# 780-00019_Rev1_Pg1.net
KiCad netlist of a schematic drawn in Altium Designer
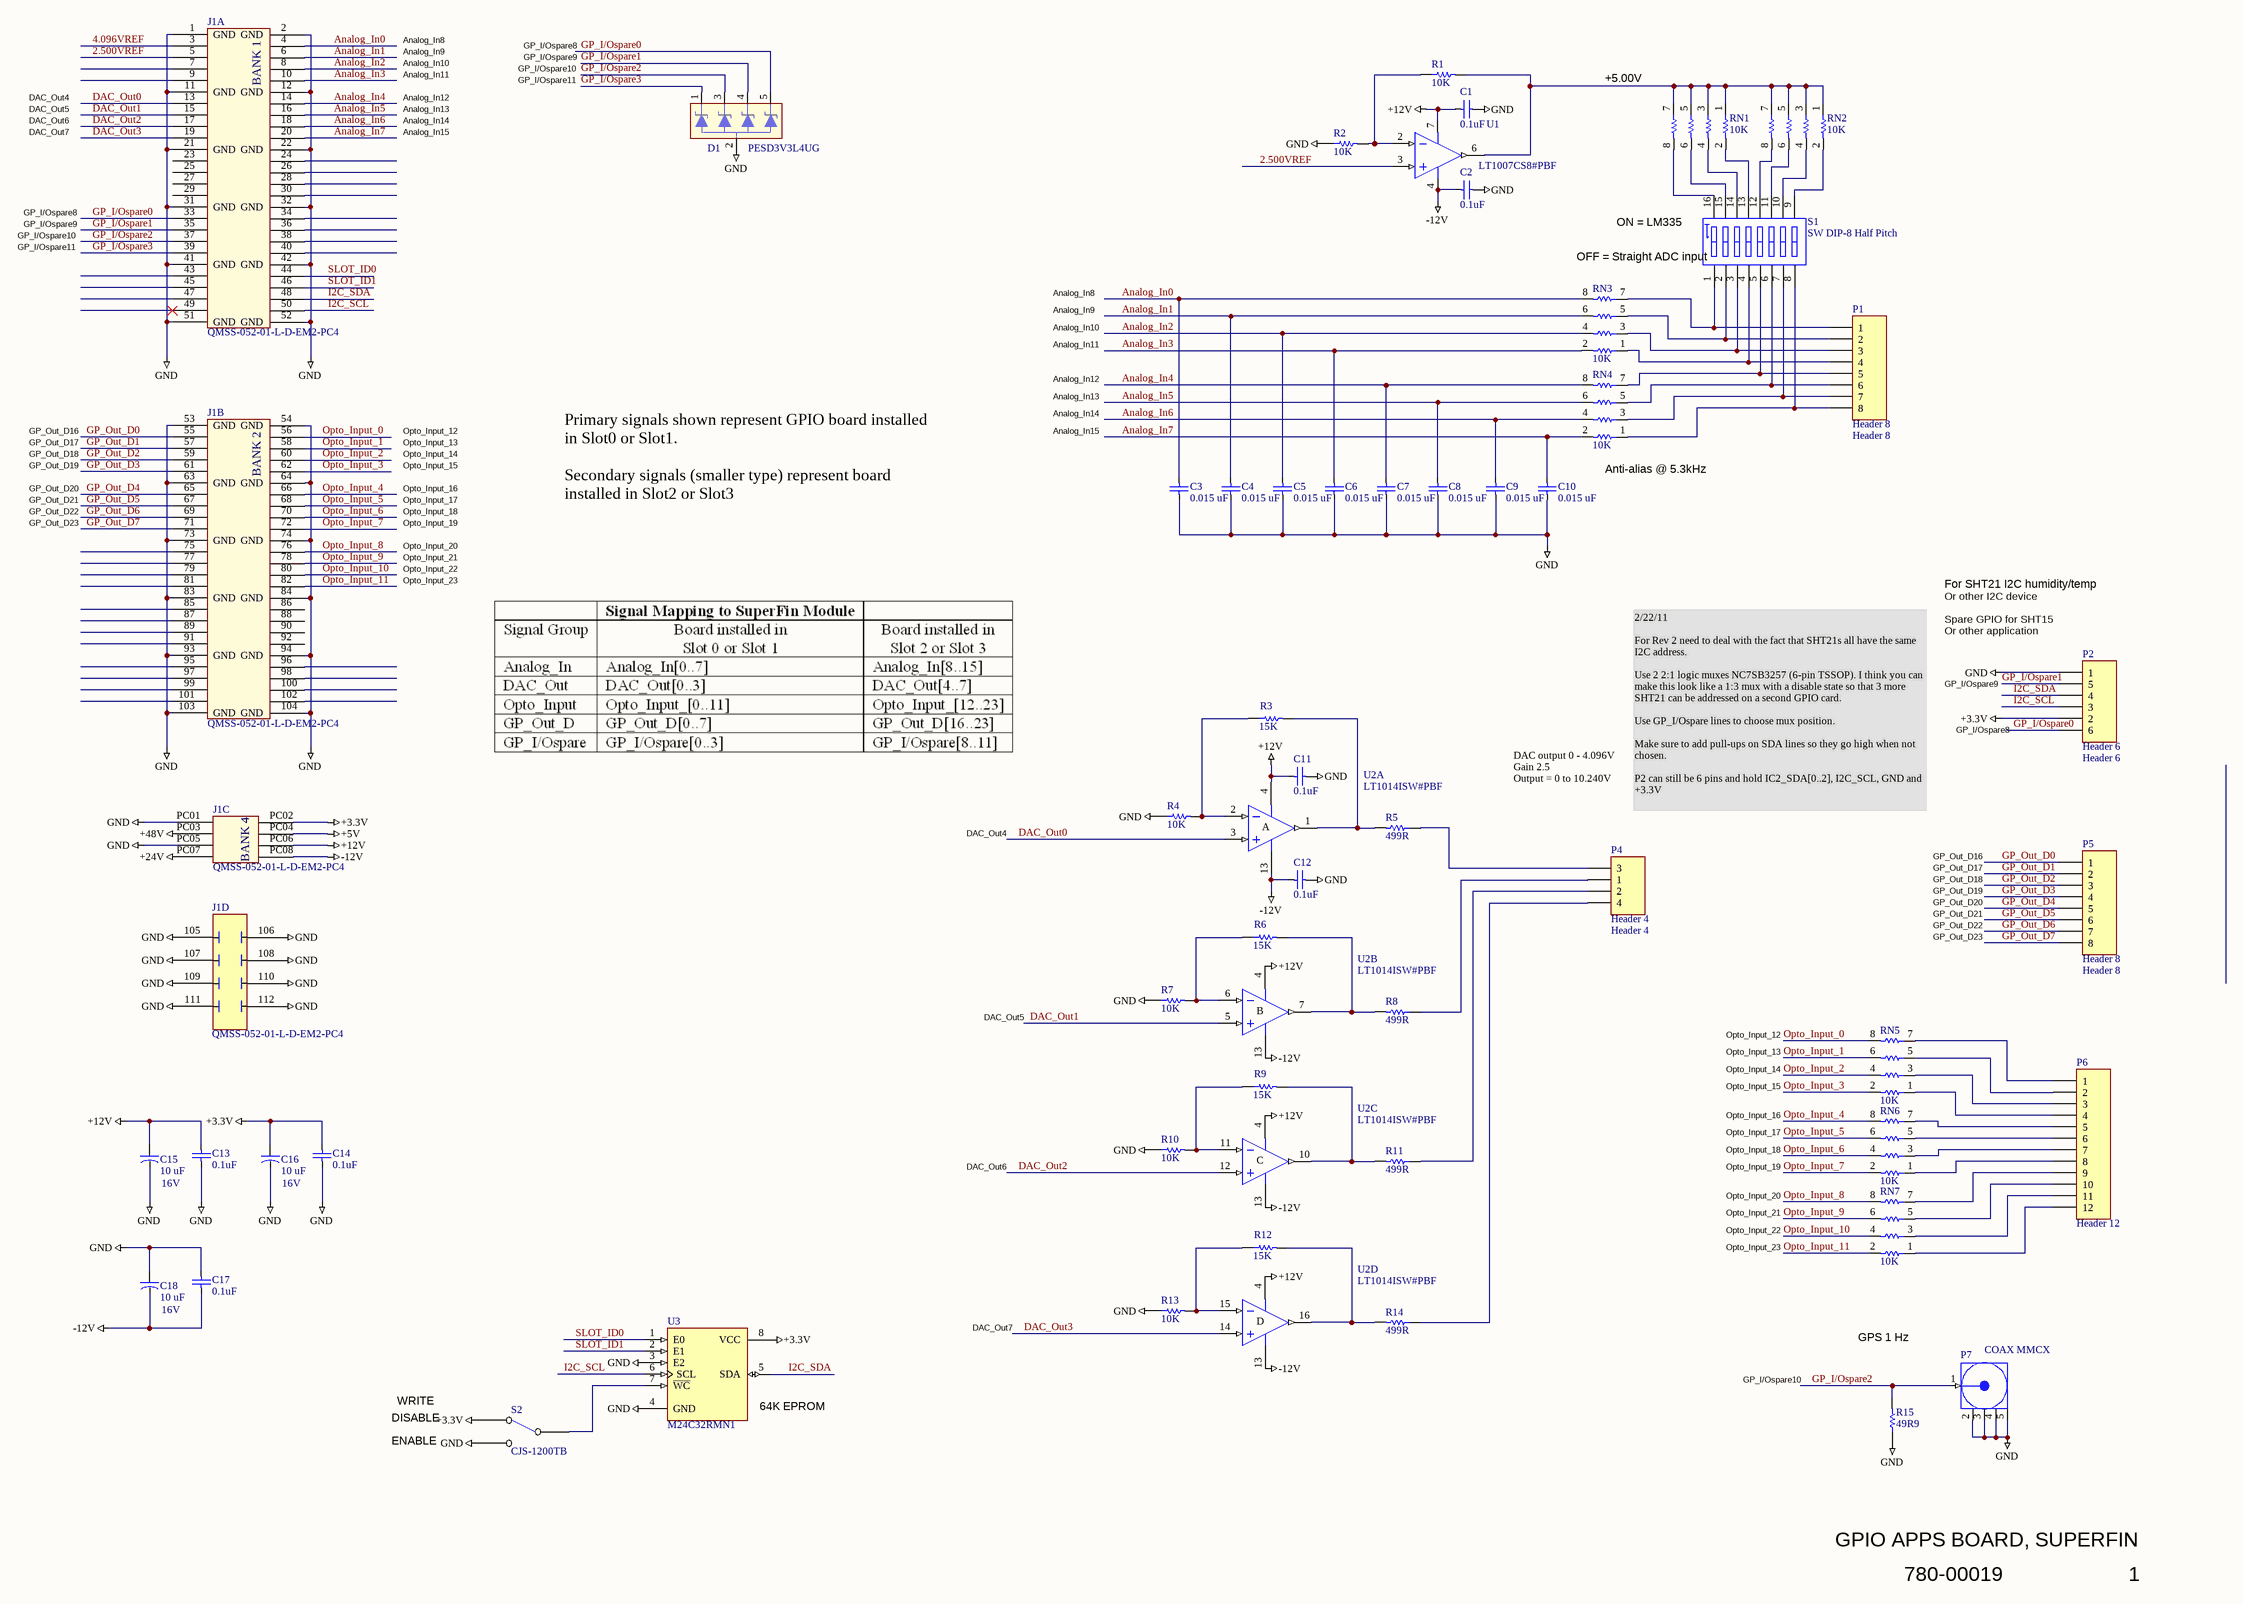
[diagram p0: 780-00019 Rev1 Pg1.SchDoc]

(export (version "E")
  (design (tool "Eeschema 10.0.6"))
  (components
    (comp (ref "C1")
      (value "0.1uF")
      (footprint "SMD_0805")
      (description "Capacitor")
      (fields (field (name "Comment") "Cap SMD"))
      (libsource (lib "Richs Schematic Components") (part "Cap SMD"))
    )
    (comp (ref "C2")
      (value "0.1uF")
      (footprint "SMD_0805")
      (description "Capacitor")
      (fields (field (name "Comment") "Cap SMD"))
      (libsource (lib "Richs Schematic Components") (part "Cap SMD"))
    )
    (comp (ref "C3")
      (value "0.015 uF")
      (footprint "SMD_0805")
      (description "Capacitor NP0")
      (fields (field (name "MANUFACTURER") "Murata") (field (name "Comment") "Cap SMD"))
      (libsource (lib "Richs Schematic Components") (part "Cap SMD"))
    )
    (comp (ref "C4")
      (value "0.015 uF")
      (footprint "SMD_0805")
      (description "Capacitor NP0")
      (fields (field (name "MANUFACTURER") "Murata") (field (name "Comment") "Cap SMD"))
      (libsource (lib "Richs Schematic Components") (part "Cap SMD"))
    )
    (comp (ref "C5")
      (value "0.015 uF")
      (footprint "SMD_0805")
      (description "Capacitor NP0")
      (fields (field (name "MANUFACTURER") "Murata") (field (name "Comment") "Cap SMD"))
      (libsource (lib "Richs Schematic Components") (part "Cap SMD"))
    )
    (comp (ref "C6")
      (value "0.015 uF")
      (footprint "SMD_0805")
      (description "Capacitor NP0")
      (fields (field (name "MANUFACTURER") "Murata") (field (name "Comment") "Cap SMD"))
      (libsource (lib "Richs Schematic Components") (part "Cap SMD"))
    )
    (comp (ref "C7")
      (value "0.015 uF")
      (footprint "SMD_0805")
      (description "Capacitor NP0")
      (fields (field (name "MANUFACTURER") "Murata") (field (name "Comment") "Cap SMD"))
      (libsource (lib "Richs Schematic Components") (part "Cap SMD"))
    )
    (comp (ref "C8")
      (value "0.015 uF")
      (footprint "SMD_0805")
      (description "Capacitor NP0")
      (fields (field (name "MANUFACTURER") "Murata") (field (name "Comment") "Cap SMD"))
      (libsource (lib "Richs Schematic Components") (part "Cap SMD"))
    )
    (comp (ref "C9")
      (value "0.015 uF")
      (footprint "SMD_0805")
      (description "Capacitor NP0")
      (fields (field (name "MANUFACTURER") "Murata") (field (name "Comment") "Cap SMD"))
      (libsource (lib "Richs Schematic Components") (part "Cap SMD"))
    )
    (comp (ref "C10")
      (value "0.015 uF")
      (footprint "SMD_0805")
      (description "Capacitor NP0")
      (fields (field (name "MANUFACTURER") "Murata") (field (name "Comment") "Cap SMD"))
      (libsource (lib "Richs Schematic Components") (part "Cap SMD"))
    )
    (comp (ref "C11")
      (value "0.1uF")
      (footprint "SMD_0805")
      (description "Capacitor")
      (fields (field (name "Comment") "Cap SMD"))
      (libsource (lib "Richs Schematic Components") (part "Cap SMD"))
    )
    (comp (ref "C12")
      (value "0.1uF")
      (footprint "SMD_0805")
      (description "Capacitor")
      (fields (field (name "Comment") "Cap SMD"))
      (libsource (lib "Richs Schematic Components") (part "Cap SMD"))
    )
    (comp (ref "C13")
      (value "0.1uF")
      (footprint "SMD_0805")
      (description "Capacitor")
      (fields (field (name "Comment") "Cap SMD"))
      (libsource (lib "Richs Schematic Components") (part "Cap SMD"))
    )
    (comp (ref "C14")
      (value "0.1uF")
      (footprint "SMD_0805")
      (description "Capacitor")
      (fields (field (name "Comment") "Cap SMD"))
      (libsource (lib "Richs Schematic Components") (part "Cap SMD"))
    )
    (comp (ref "C15")
      (value "16V")
      (footprint "SMD_CAP_3216")
      (description "outline 3.2mm x 1.6mm")
      (fields (field (name "MANUFACTURER") "KEMET") (field (name "ALTIUM_VALUE") "10 uF"))
      (libsource (lib "Richs Schematic Components") (part "Cap Tant 16V"))
    )
    (comp (ref "C16")
      (value "16V")
      (footprint "SMD_CAP_3216")
      (description "outline 3.2mm x 1.6mm")
      (fields (field (name "MANUFACTURER") "KEMET") (field (name "ALTIUM_VALUE") "10 uF"))
      (libsource (lib "Richs Schematic Components") (part "Cap Tant 16V"))
    )
    (comp (ref "C17")
      (value "0.1uF")
      (footprint "SMD_0805")
      (description "Capacitor")
      (fields (field (name "Comment") "Cap SMD"))
      (libsource (lib "Richs Schematic Components") (part "Cap SMD"))
    )
    (comp (ref "C18")
      (value "16V")
      (footprint "SMD_CAP_3216")
      (description "outline 3.2mm x 1.6mm")
      (fields (field (name "MANUFACTURER") "KEMET") (field (name "ALTIUM_VALUE") "10 uF"))
      (libsource (lib "Richs Schematic Components") (part "Cap Tant 16V"))
    )
    (comp (ref "D1")
      (value "PESD3V3L4UG")
      (footprint "SOT-353")
      (description "Quad ESD Diode 3.3V")
      (fields (field (name "MANUFACTURER") "NXP"))
      (libsource (lib "Richs Schematic Components") (part "ESD Diode 3.3V Quad"))
    )
    (comp (ref "J1")
      (value "QMSS-052-01-L-D-EM2-PC4")
      (footprint "QMS EDGE PWR PINS - 104 pin")
      (description "SAMTEC QMSS EDGE W/PWR PINS")
      (fields (field (name "MANUFACTURER") "SAMTEC") (field (name "Comment") "QMSS-EM-PC4-104pin"))
      (libsource (lib "Richs Schematic Components") (part "QMSS-EM-PC4-104pin"))
    )
    (comp (ref "P1")
      (value "Header 8")
      (footprint "HDR1X8 for IDC")
      (description "Header, 8-Pin")
      (fields (field (name "ALTIUM_VALUE") "Header 8"))
      (libsource (lib "Richs Schematic Components") (part "Header 8"))
    )
    (comp (ref "P2")
      (value "Header 6")
      (footprint "HDR1X6 for IDC")
      (description "Header, 6-Pin")
      (fields (field (name "ALTIUM_VALUE") "Header 6"))
      (libsource (lib "Richs Schematic Components") (part "Header 6"))
    )
    (comp (ref "P4")
      (value "Header 4")
      (footprint "HDR1X4 for IDC")
      (description "Header, 4-Pin")
      (fields (field (name "ALTIUM_VALUE") "Header 4"))
      (libsource (lib "Richs Schematic Components") (part "Header 4"))
    )
    (comp (ref "P5")
      (value "Header 8")
      (footprint "HDR1X8 for IDC")
      (description "Header, 8-Pin")
      (fields (field (name "ALTIUM_VALUE") "Header 8"))
      (libsource (lib "Richs Schematic Components") (part "Header 8"))
    )
    (comp (ref "P6")
      (value "Header 12")
      (footprint "HDR1X12 for IDC")
      (description "Header, 12-Pin")
      (fields (field (name "MANUFACTURER") "Tyco"))
      (libsource (lib "Richs Schematic Components") (part "Header 12"))
    )
    (comp (ref "P7")
      (value "COAX MMCX")
      (footprint "Miscellaneous Connectors:MMCX2.54-V5")
      (description "RF Coaxial PCB Connector, MMCX; Thru-Hole, Vertical Mount Plug,  50 Ohm Impedance")
      (fields (field (name "MANUFACTURER") "Emerson"))
      (libsource (lib "Richs Schematic Components") (part "COAX-M"))
    )
    (comp (ref "R1")
      (value "10K")
      (footprint "SMD_0805")
      (description "Resistor 0805")
      (fields (field (name "MANUFACTURER") "Vishay/Dale") (field (name "Comment") "Res 0805"))
      (libsource (lib "Richs Schematic Components") (part "Res SMD"))
    )
    (comp (ref "R2")
      (value "10K")
      (footprint "SMD_0805")
      (description "Resistor 0805")
      (fields (field (name "MANUFACTURER") "Vishay/Dale") (field (name "Comment") "Res 0805"))
      (libsource (lib "Richs Schematic Components") (part "Res SMD"))
    )
    (comp (ref "R3")
      (value "15K")
      (footprint "SMD_0805")
      (description "Resistor 0805")
      (fields (field (name "MANUFACTURER") "Vishay/Dale") (field (name "Comment") "Res 0805"))
      (libsource (lib "Richs Schematic Components") (part "Res SMD"))
    )
    (comp (ref "R4")
      (value "10K")
      (footprint "SMD_0805")
      (description "Resistor 0805")
      (fields (field (name "MANUFACTURER") "Vishay/Dale") (field (name "Comment") "Res 0805"))
      (libsource (lib "Richs Schematic Components") (part "Res SMD"))
    )
    (comp (ref "R5")
      (value "499R")
      (footprint "SMD_0805")
      (description "Resistor 0805")
      (fields (field (name "MANUFACTURER") "Vishay/Dale") (field (name "Comment") "Res 0805"))
      (libsource (lib "Richs Schematic Components") (part "Res SMD"))
    )
    (comp (ref "R6")
      (value "15K")
      (footprint "SMD_0805")
      (description "Resistor 0805")
      (fields (field (name "MANUFACTURER") "Vishay/Dale") (field (name "Comment") "Res 0805"))
      (libsource (lib "Richs Schematic Components") (part "Res SMD"))
    )
    (comp (ref "R7")
      (value "10K")
      (footprint "SMD_0805")
      (description "Resistor 0805")
      (fields (field (name "MANUFACTURER") "Vishay/Dale") (field (name "Comment") "Res 0805"))
      (libsource (lib "Richs Schematic Components") (part "Res SMD"))
    )
    (comp (ref "R8")
      (value "499R")
      (footprint "SMD_0805")
      (description "Resistor 0805")
      (fields (field (name "MANUFACTURER") "Vishay/Dale") (field (name "Comment") "Res 0805"))
      (libsource (lib "Richs Schematic Components") (part "Res SMD"))
    )
    (comp (ref "R9")
      (value "15K")
      (footprint "SMD_0805")
      (description "Resistor 0805")
      (fields (field (name "MANUFACTURER") "Vishay/Dale") (field (name "Comment") "Res 0805"))
      (libsource (lib "Richs Schematic Components") (part "Res SMD"))
    )
    (comp (ref "R10")
      (value "10K")
      (footprint "SMD_0805")
      (description "Resistor 0805")
      (fields (field (name "MANUFACTURER") "Vishay/Dale") (field (name "Comment") "Res 0805"))
      (libsource (lib "Richs Schematic Components") (part "Res SMD"))
    )
    (comp (ref "R11")
      (value "499R")
      (footprint "SMD_0805")
      (description "Resistor 0805")
      (fields (field (name "MANUFACTURER") "Vishay/Dale") (field (name "Comment") "Res 0805"))
      (libsource (lib "Richs Schematic Components") (part "Res SMD"))
    )
    (comp (ref "R12")
      (value "15K")
      (footprint "SMD_0805")
      (description "Resistor 0805")
      (fields (field (name "MANUFACTURER") "Vishay/Dale") (field (name "Comment") "Res 0805"))
      (libsource (lib "Richs Schematic Components") (part "Res SMD"))
    )
    (comp (ref "R13")
      (value "10K")
      (footprint "SMD_0805")
      (description "Resistor 0805")
      (fields (field (name "MANUFACTURER") "Vishay/Dale") (field (name "Comment") "Res 0805"))
      (libsource (lib "Richs Schematic Components") (part "Res SMD"))
    )
    (comp (ref "R14")
      (value "499R")
      (footprint "SMD_0805")
      (description "Resistor 0805")
      (fields (field (name "MANUFACTURER") "Vishay/Dale") (field (name "Comment") "Res 0805"))
      (libsource (lib "Richs Schematic Components") (part "Res SMD"))
    )
    (comp (ref "R15")
      (value "49R9")
      (footprint "SMD_0805")
      (description "Resistor 0805")
      (fields (field (name "MANUFACTURER") "Vishay/Dale") (field (name "Comment") "Res 0805"))
      (libsource (lib "Richs Schematic Components") (part "Res SMD"))
    )
    (comp (ref "RN1")
      (value "10K")
      (footprint "RES ARRAY 0603 x 4")
      (description "Resistor Array 4 Isolated")
      (fields (field (name "MANUFACTURER") "PANASONIC - ECG") (field (name "Comment") "RES ARRAY  x4 10K"))
      (libsource (lib "Richs Schematic Components") (part "RES ARRAY  x4 10K"))
    )
    (comp (ref "RN2")
      (value "10K")
      (footprint "RES ARRAY 0603 x 4")
      (description "Resistor Array 4 Isolated")
      (fields (field (name "MANUFACTURER") "PANASONIC - ECG") (field (name "Comment") "RES ARRAY  x4 10K"))
      (libsource (lib "Richs Schematic Components") (part "RES ARRAY  x4 10K"))
    )
    (comp (ref "RN3")
      (value "10K")
      (footprint "RES ARRAY 0603 x 4")
      (description "Resistor Array 4 Isolated")
      (fields (field (name "MANUFACTURER") "PANASONIC - ECG") (field (name "Comment") "RES ARRAY  x4 10K"))
      (libsource (lib "Richs Schematic Components") (part "RES ARRAY  x4 10K"))
    )
    (comp (ref "RN4")
      (value "10K")
      (footprint "RES ARRAY 0603 x 4")
      (description "Resistor Array 4 Isolated")
      (fields (field (name "MANUFACTURER") "PANASONIC - ECG") (field (name "Comment") "RES ARRAY  x4 10K"))
      (libsource (lib "Richs Schematic Components") (part "RES ARRAY  x4 10K"))
    )
    (comp (ref "RN5")
      (value "10K")
      (footprint "RES ARRAY 0603 x 4")
      (description "Resistor Array 4 Isolated")
      (fields (field (name "MANUFACTURER") "PANASONIC - ECG") (field (name "Comment") "RES ARRAY  x4 10K"))
      (libsource (lib "Richs Schematic Components") (part "RES ARRAY  x4 10K"))
    )
    (comp (ref "RN6")
      (value "10K")
      (footprint "RES ARRAY 0603 x 4")
      (description "Resistor Array 4 Isolated")
      (fields (field (name "MANUFACTURER") "PANASONIC - ECG") (field (name "Comment") "RES ARRAY  x4 10K"))
      (libsource (lib "Richs Schematic Components") (part "RES ARRAY  x4 10K"))
    )
    (comp (ref "RN7")
      (value "10K")
      (footprint "RES ARRAY 0603 x 4")
      (description "Resistor Array 4 Isolated")
      (fields (field (name "MANUFACTURER") "PANASONIC - ECG") (field (name "Comment") "RES ARRAY  x4 10K"))
      (libsource (lib "Richs Schematic Components") (part "RES ARRAY  x4 10K"))
    )
    (comp (ref "S1")
      (value "SW DIP-8 Half Pitch")
      (footprint "SW DIP 8 pos half pitch")
      (description "DIP Switch, 8 Position, SPST")
      (fields (field (name "MANUFACTURER") "GrayHill"))
      (libsource (lib "Richs Schematic Components") (part "SW DIP-8 Half Pitch"))
    )
    (comp (ref "S2")
      (value "CJS-1200TB")
      (footprint "CAS-120B")
      (fields (field (name "MANUFACTURER") "Copal Electronics"))
      (libsource (lib "JON_1_Library") (part "SW_SPDT_DOUG"))
    )
    (comp (ref "U1")
      (value "LT1007CS8#PBF")
      (footprint "S8_M")
      (description "Low Noise BJT input opamp")
      (fields (field (name "MANUFACTURER") "Linear Tech"))
      (libsource (lib "Richs Schematic Components") (part "LT1007CS8#PBF"))
    )
    (comp (ref "U2")
      (value "LT1014ISW#PBF")
      (footprint "SW16_N")
      (description "Quad Precision Operational Amplifier")
      (fields (field (name "MANUFACTURER") "Linear Tech"))
      (libsource (lib "LT Operational Amplifier") (part "LT1014ISW#PBF"))
    )
    (comp (ref "U3")
      (value "M24C32RMN1")
      (footprint "SOP8_N")
      (description "32 Kbit Serial I²C Bus EEPROM")
      (fields (field (name "MANUFACTURER") "ST Micro"))
      (libsource (lib "ST Memory EEPROM Serial") (part "M24C32RMN1"))
    )
  )
  (nets
    (net (code "1") (name "+3.3V") (class "Default")
      (node (ref "C14") (pin "1") (pinfunction "1_1") (pintype "passive"))
      (node (ref "C16") (pin "1") (pinfunction "1_1") (pintype "passive"))
      (node (ref "J1") (pin "PC02") (pinfunction "PC02_PC02") (pintype "passive"))
      (node (ref "P2") (pin "2") (pinfunction "2_2") (pintype "passive"))
      (node (ref "S2") (pin "3") (pinfunction "NC_3") (pintype "passive"))
      (node (ref "U3") (pin "8") (pinfunction "VCC_8") (pintype "power_in"))
    )
    (net (code "2") (name "+5V") (class "Default")
      (node (ref "J1") (pin "PC04") (pinfunction "PC04_PC04") (pintype "passive"))
    )
    (net (code "3") (name "+12V") (class "Default")
      (node (ref "C1") (pin "1") (pinfunction "1_1") (pintype "passive"))
      (node (ref "C11") (pin "1") (pinfunction "1_1") (pintype "passive"))
      (node (ref "C13") (pin "1") (pinfunction "1_1") (pintype "passive"))
      (node (ref "C15") (pin "1") (pinfunction "1_1") (pintype "passive"))
      (node (ref "J1") (pin "PC06") (pinfunction "PC06_PC06") (pintype "passive"))
      (node (ref "U1") (pin "7") (pinfunction "V+_7") (pintype "power_in"))
      (node (ref "U2") (pin "4") (pinfunction "V+_4") (pintype "power_in"))
    )
    (net (code "4") (name "+24V") (class "Default")
      (node (ref "J1") (pin "PC07") (pinfunction "PC07_PC07") (pintype "passive"))
    )
    (net (code "5") (name "+48V") (class "Default")
      (node (ref "J1") (pin "PC03") (pinfunction "PC03_PC03") (pintype "passive"))
    )
    (net (code "6") (name "-12V") (class "Default")
      (node (ref "C12") (pin "1") (pinfunction "1_1") (pintype "passive"))
      (node (ref "C17") (pin "2") (pinfunction "2_2") (pintype "passive"))
      (node (ref "C18") (pin "2") (pinfunction "2_2") (pintype "passive"))
      (node (ref "C2") (pin "1") (pinfunction "1_1") (pintype "passive"))
      (node (ref "J1") (pin "PC08") (pinfunction "PC08_PC08") (pintype "passive"))
      (node (ref "U1") (pin "4") (pinfunction "V-_4") (pintype "power_in"))
      (node (ref "U2") (pin "13") (pinfunction "V-_13") (pintype "power_in"))
    )
    (net (code "7") (name "/2.500VREF") (class "Default")
      (node (ref "J1") (pin "5") (pinfunction "5_5") (pintype "passive"))
      (node (ref "U1") (pin "3") (pinfunction "IN+_3") (pintype "input"))
    )
    (net (code "8") (name "/4.096VREF") (class "Default")
      (node (ref "J1") (pin "3") (pinfunction "3_3") (pintype "passive"))
    )
    (net (code "9") (name "/Analog_In0") (class "Default")
      (node (ref "C3") (pin "2") (pinfunction "2_2") (pintype "passive"))
      (node (ref "J1") (pin "4") (pinfunction "4_4") (pintype "passive"))
      (node (ref "RN3") (pin "8") (pinfunction "8_8") (pintype "passive"))
    )
    (net (code "10") (name "/Analog_In1") (class "Default")
      (node (ref "C4") (pin "2") (pinfunction "2_2") (pintype "passive"))
      (node (ref "J1") (pin "6") (pinfunction "6_6") (pintype "passive"))
      (node (ref "RN3") (pin "6") (pinfunction "6_6") (pintype "passive"))
    )
    (net (code "11") (name "/Analog_In2") (class "Default")
      (node (ref "C5") (pin "2") (pinfunction "2_2") (pintype "passive"))
      (node (ref "J1") (pin "8") (pinfunction "8_8") (pintype "passive"))
      (node (ref "RN3") (pin "4") (pinfunction "4_4") (pintype "passive"))
    )
    (net (code "12") (name "/Analog_In3") (class "Default")
      (node (ref "C6") (pin "2") (pinfunction "2_2") (pintype "passive"))
      (node (ref "J1") (pin "10") (pinfunction "10_10") (pintype "passive"))
      (node (ref "RN3") (pin "2") (pinfunction "2_2") (pintype "passive"))
    )
    (net (code "13") (name "/Analog_In4") (class "Default")
      (node (ref "C7") (pin "2") (pinfunction "2_2") (pintype "passive"))
      (node (ref "J1") (pin "14") (pinfunction "14_14") (pintype "passive"))
      (node (ref "RN4") (pin "8") (pinfunction "8_8") (pintype "passive"))
    )
    (net (code "14") (name "/Analog_In5") (class "Default")
      (node (ref "C8") (pin "2") (pinfunction "2_2") (pintype "passive"))
      (node (ref "J1") (pin "16") (pinfunction "16_16") (pintype "passive"))
      (node (ref "RN4") (pin "6") (pinfunction "6_6") (pintype "passive"))
    )
    (net (code "15") (name "/Analog_In6") (class "Default")
      (node (ref "C9") (pin "2") (pinfunction "2_2") (pintype "passive"))
      (node (ref "J1") (pin "18") (pinfunction "18_18") (pintype "passive"))
      (node (ref "RN4") (pin "4") (pinfunction "4_4") (pintype "passive"))
    )
    (net (code "16") (name "/Analog_In7") (class "Default")
      (node (ref "C10") (pin "2") (pinfunction "2_2") (pintype "passive"))
      (node (ref "J1") (pin "20") (pinfunction "20_20") (pintype "passive"))
      (node (ref "RN4") (pin "2") (pinfunction "2_2") (pintype "passive"))
    )
    (net (code "17") (name "/DAC_Out0") (class "Default")
      (node (ref "J1") (pin "13") (pinfunction "13_13") (pintype "passive"))
      (node (ref "U2") (pin "3") (pinfunction "IN+_3") (pintype "input"))
    )
    (net (code "18") (name "/DAC_Out1") (class "Default")
      (node (ref "J1") (pin "15") (pinfunction "15_15") (pintype "passive"))
      (node (ref "U2") (pin "5") (pinfunction "IN+_5") (pintype "input"))
    )
    (net (code "19") (name "/DAC_Out2") (class "Default")
      (node (ref "J1") (pin "17") (pinfunction "17_17") (pintype "passive"))
      (node (ref "U2") (pin "12") (pinfunction "IN+_12") (pintype "input"))
    )
    (net (code "20") (name "/DAC_Out3") (class "Default")
      (node (ref "J1") (pin "19") (pinfunction "19_19") (pintype "passive"))
      (node (ref "U2") (pin "14") (pinfunction "IN+_14") (pintype "input"))
    )
    (net (code "21") (name "/GP_I{slash}Ospare0") (class "Default")
      (node (ref "D1") (pin "5") (pintype "passive"))
      (node (ref "J1") (pin "33") (pinfunction "33_33") (pintype "passive"))
      (node (ref "P2") (pin "6") (pinfunction "6_6") (pintype "passive"))
    )
    (net (code "22") (name "/GP_I{slash}Ospare1") (class "Default")
      (node (ref "D1") (pin "4") (pintype "passive"))
      (node (ref "J1") (pin "35") (pinfunction "35_35") (pintype "passive"))
      (node (ref "P2") (pin "5") (pinfunction "5_5") (pintype "passive"))
    )
    (net (code "23") (name "/GP_I{slash}Ospare2") (class "Default")
      (node (ref "D1") (pin "3") (pintype "passive"))
      (node (ref "J1") (pin "37") (pinfunction "37_37") (pintype "passive"))
      (node (ref "P7") (pin "1") (pinfunction "Signal_1") (pintype "input"))
      (node (ref "R15") (pin "2") (pinfunction "2_2") (pintype "passive"))
    )
    (net (code "24") (name "/GP_I{slash}Ospare3") (class "Default")
      (node (ref "D1") (pin "1") (pintype "passive"))
      (node (ref "J1") (pin "39") (pinfunction "39_39") (pintype "passive"))
    )
    (net (code "25") (name "/GP_Out_D0") (class "Default")
      (node (ref "J1") (pin "55") (pinfunction "55_55") (pintype "passive"))
      (node (ref "P5") (pin "1") (pinfunction "1_1") (pintype "passive"))
    )
    (net (code "26") (name "/GP_Out_D1") (class "Default")
      (node (ref "J1") (pin "57") (pinfunction "57_57") (pintype "passive"))
      (node (ref "P5") (pin "2") (pinfunction "2_2") (pintype "passive"))
    )
    (net (code "27") (name "/GP_Out_D2") (class "Default")
      (node (ref "J1") (pin "59") (pinfunction "59_59") (pintype "passive"))
      (node (ref "P5") (pin "3") (pinfunction "3_3") (pintype "passive"))
    )
    (net (code "28") (name "/GP_Out_D3") (class "Default")
      (node (ref "J1") (pin "61") (pinfunction "61_61") (pintype "passive"))
      (node (ref "P5") (pin "4") (pinfunction "4_4") (pintype "passive"))
    )
    (net (code "29") (name "/GP_Out_D4") (class "Default")
      (node (ref "J1") (pin "65") (pinfunction "65_65") (pintype "passive"))
      (node (ref "P5") (pin "5") (pinfunction "5_5") (pintype "passive"))
    )
    (net (code "30") (name "/GP_Out_D5") (class "Default")
      (node (ref "J1") (pin "67") (pinfunction "67_67") (pintype "passive"))
      (node (ref "P5") (pin "6") (pinfunction "6_6") (pintype "passive"))
    )
    (net (code "31") (name "/GP_Out_D6") (class "Default")
      (node (ref "J1") (pin "69") (pinfunction "69_69") (pintype "passive"))
      (node (ref "P5") (pin "7") (pinfunction "7_7") (pintype "passive"))
    )
    (net (code "32") (name "/GP_Out_D7") (class "Default")
      (node (ref "J1") (pin "71") (pinfunction "71_71") (pintype "passive"))
      (node (ref "P5") (pin "8") (pinfunction "8_8") (pintype "passive"))
    )
    (net (code "33") (name "/I2C_SCL") (class "Default")
      (node (ref "J1") (pin "50") (pinfunction "50_50") (pintype "passive"))
      (node (ref "P2") (pin "3") (pinfunction "3_3") (pintype "passive"))
      (node (ref "U3") (pin "6") (pinfunction "SCL_6") (pintype "input"))
    )
    (net (code "34") (name "/I2C_SDA") (class "Default")
      (node (ref "J1") (pin "48") (pinfunction "48_48") (pintype "passive"))
      (node (ref "P2") (pin "4") (pinfunction "4_4") (pintype "passive"))
      (node (ref "U3") (pin "5") (pinfunction "SDA_5") (pintype "bidirectional"))
    )
    (net (code "35") (name "/Opto_Input_0") (class "Default")
      (node (ref "J1") (pin "56") (pinfunction "56_56") (pintype "passive"))
      (node (ref "RN5") (pin "8") (pinfunction "8_8") (pintype "passive"))
    )
    (net (code "36") (name "/Opto_Input_1") (class "Default")
      (node (ref "J1") (pin "58") (pinfunction "58_58") (pintype "passive"))
      (node (ref "RN5") (pin "6") (pinfunction "6_6") (pintype "passive"))
    )
    (net (code "37") (name "/Opto_Input_2") (class "Default")
      (node (ref "J1") (pin "60") (pinfunction "60_60") (pintype "passive"))
      (node (ref "RN5") (pin "4") (pinfunction "4_4") (pintype "passive"))
    )
    (net (code "38") (name "/Opto_Input_3") (class "Default")
      (node (ref "J1") (pin "62") (pinfunction "62_62") (pintype "passive"))
      (node (ref "RN5") (pin "2") (pinfunction "2_2") (pintype "passive"))
    )
    (net (code "39") (name "/Opto_Input_4") (class "Default")
      (node (ref "J1") (pin "66") (pinfunction "66_66") (pintype "passive"))
      (node (ref "RN6") (pin "8") (pinfunction "8_8") (pintype "passive"))
    )
    (net (code "40") (name "/Opto_Input_5") (class "Default")
      (node (ref "J1") (pin "68") (pinfunction "68_68") (pintype "passive"))
      (node (ref "RN6") (pin "6") (pinfunction "6_6") (pintype "passive"))
    )
    (net (code "41") (name "/Opto_Input_6") (class "Default")
      (node (ref "J1") (pin "70") (pinfunction "70_70") (pintype "passive"))
      (node (ref "RN6") (pin "4") (pinfunction "4_4") (pintype "passive"))
    )
    (net (code "42") (name "/Opto_Input_7") (class "Default")
      (node (ref "J1") (pin "72") (pinfunction "72_72") (pintype "passive"))
      (node (ref "RN6") (pin "2") (pinfunction "2_2") (pintype "passive"))
    )
    (net (code "43") (name "/Opto_Input_8") (class "Default")
      (node (ref "J1") (pin "76") (pinfunction "76_76") (pintype "passive"))
      (node (ref "RN7") (pin "8") (pinfunction "8_8") (pintype "passive"))
    )
    (net (code "44") (name "/Opto_Input_9") (class "Default")
      (node (ref "J1") (pin "78") (pinfunction "78_78") (pintype "passive"))
      (node (ref "RN7") (pin "6") (pinfunction "6_6") (pintype "passive"))
    )
    (net (code "45") (name "/Opto_Input_10") (class "Default")
      (node (ref "J1") (pin "80") (pinfunction "80_80") (pintype "passive"))
      (node (ref "RN7") (pin "4") (pinfunction "4_4") (pintype "passive"))
    )
    (net (code "46") (name "/Opto_Input_11") (class "Default")
      (node (ref "J1") (pin "82") (pinfunction "82_82") (pintype "passive"))
      (node (ref "RN7") (pin "2") (pinfunction "2_2") (pintype "passive"))
    )
    (net (code "47") (name "/SLOT_ID0") (class "Default")
      (node (ref "J1") (pin "44") (pinfunction "44_44") (pintype "passive"))
      (node (ref "U3") (pin "1") (pinfunction "E0_1") (pintype "input"))
    )
    (net (code "48") (name "/SLOT_ID1") (class "Default")
      (node (ref "J1") (pin "46") (pinfunction "46_46") (pintype "passive"))
      (node (ref "U3") (pin "2") (pinfunction "E1_2") (pintype "input"))
    )
    (net (code "49") (name "GND") (class "Default")
      (node (ref "C1") (pin "2") (pinfunction "2_2") (pintype "passive"))
      (node (ref "C10") (pin "1") (pinfunction "1_1") (pintype "passive"))
      (node (ref "C11") (pin "2") (pinfunction "2_2") (pintype "passive"))
      (node (ref "C12") (pin "2") (pinfunction "2_2") (pintype "passive"))
      (node (ref "C13") (pin "2") (pinfunction "2_2") (pintype "passive"))
      (node (ref "C14") (pin "2") (pinfunction "2_2") (pintype "passive"))
      (node (ref "C15") (pin "2") (pinfunction "2_2") (pintype "passive"))
      (node (ref "C16") (pin "2") (pinfunction "2_2") (pintype "passive"))
      (node (ref "C17") (pin "1") (pinfunction "1_1") (pintype "passive"))
      (node (ref "C18") (pin "1") (pinfunction "1_1") (pintype "passive"))
      (node (ref "C2") (pin "2") (pinfunction "2_2") (pintype "passive"))
      (node (ref "C3") (pin "1") (pinfunction "1_1") (pintype "passive"))
      (node (ref "C4") (pin "1") (pinfunction "1_1") (pintype "passive"))
      (node (ref "C5") (pin "1") (pinfunction "1_1") (pintype "passive"))
      (node (ref "C6") (pin "1") (pinfunction "1_1") (pintype "passive"))
      (node (ref "C7") (pin "1") (pinfunction "1_1") (pintype "passive"))
      (node (ref "C8") (pin "1") (pinfunction "1_1") (pintype "passive"))
      (node (ref "C9") (pin "1") (pinfunction "1_1") (pintype "passive"))
      (node (ref "D1") (pin "2") (pintype "passive"))
      (node (ref "J1") (pin "1") (pinfunction "GND_1") (pintype "passive"))
      (node (ref "J1") (pin "103") (pinfunction "GND_103") (pintype "passive"))
      (node (ref "J1") (pin "104") (pinfunction "GND_104") (pintype "passive"))
      (node (ref "J1") (pin "105") (pinfunction "GND_105") (pintype "passive"))
      (node (ref "J1") (pin "106") (pinfunction "GND_106") (pintype "passive"))
      (node (ref "J1") (pin "107") (pinfunction "GND_107") (pintype "passive"))
      (node (ref "J1") (pin "108") (pinfunction "GND_108") (pintype "passive"))
      (node (ref "J1") (pin "109") (pinfunction "GND_109") (pintype "passive"))
      (node (ref "J1") (pin "11") (pinfunction "GND_11") (pintype "passive"))
      (node (ref "J1") (pin "110") (pinfunction "GND_110") (pintype "passive"))
      (node (ref "J1") (pin "111") (pinfunction "GND_111") (pintype "passive"))
      (node (ref "J1") (pin "112") (pinfunction "GND_112") (pintype "passive"))
      (node (ref "J1") (pin "12") (pinfunction "GND_12") (pintype "passive"))
      (node (ref "J1") (pin "2") (pinfunction "GND_2") (pintype "passive"))
      (node (ref "J1") (pin "21") (pinfunction "GND_21") (pintype "passive"))
      (node (ref "J1") (pin "22") (pinfunction "GND_22") (pintype "passive"))
      (node (ref "J1") (pin "31") (pinfunction "GND_31") (pintype "passive"))
      (node (ref "J1") (pin "32") (pinfunction "GND_32") (pintype "passive"))
      (node (ref "J1") (pin "41") (pinfunction "GND_41") (pintype "passive"))
      (node (ref "J1") (pin "42") (pinfunction "GND_42") (pintype "passive"))
      (node (ref "J1") (pin "51") (pinfunction "GND_51") (pintype "passive"))
      (node (ref "J1") (pin "52") (pinfunction "GND_52") (pintype "passive"))
      (node (ref "J1") (pin "53") (pinfunction "GND_53") (pintype "passive"))
      (node (ref "J1") (pin "54") (pinfunction "GND_54") (pintype "passive"))
      (node (ref "J1") (pin "63") (pinfunction "GND_63") (pintype "passive"))
      (node (ref "J1") (pin "64") (pinfunction "GND_64") (pintype "passive"))
      (node (ref "J1") (pin "73") (pinfunction "GND_73") (pintype "passive"))
      (node (ref "J1") (pin "74") (pinfunction "GND_74") (pintype "passive"))
      (node (ref "J1") (pin "83") (pinfunction "GND_83") (pintype "passive"))
      (node (ref "J1") (pin "84") (pinfunction "GND_84") (pintype "passive"))
      (node (ref "J1") (pin "93") (pinfunction "GND_93") (pintype "passive"))
      (node (ref "J1") (pin "94") (pinfunction "GND_94") (pintype "passive"))
      (node (ref "J1") (pin "PC01") (pinfunction "PC01_PC01") (pintype "passive"))
      (node (ref "J1") (pin "PC05") (pinfunction "PC05_PC05") (pintype "passive"))
      (node (ref "P2") (pin "1") (pinfunction "1_1") (pintype "passive"))
      (node (ref "P7") (pin "2") (pinfunction "GND_2") (pintype "power_in"))
      (node (ref "P7") (pin "3") (pinfunction "GND_3") (pintype "power_in"))
      (node (ref "P7") (pin "4") (pinfunction "GND_4") (pintype "power_in"))
      (node (ref "P7") (pin "5") (pinfunction "GND_5") (pintype "power_in"))
      (node (ref "R10") (pin "1") (pinfunction "1_1") (pintype "passive"))
      (node (ref "R13") (pin "1") (pinfunction "1_1") (pintype "passive"))
      (node (ref "R15") (pin "1") (pinfunction "1_1") (pintype "passive"))
      (node (ref "R2") (pin "1") (pinfunction "1_1") (pintype "passive"))
      (node (ref "R4") (pin "1") (pinfunction "1_1") (pintype "passive"))
      (node (ref "R7") (pin "1") (pinfunction "1_1") (pintype "passive"))
      (node (ref "S2") (pin "1") (pinfunction "NO_1") (pintype "passive"))
      (node (ref "U3") (pin "3") (pinfunction "E2_3") (pintype "input"))
      (node (ref "U3") (pin "4") (pinfunction "GND_4") (pintype "power_in"))
    )
    (net (code "50") (name "Net-(P4-Pad1)") (class "Default")
      (node (ref "P4") (pin "1") (pinfunction "1_1") (pintype "passive"))
      (node (ref "R8") (pin "1") (pinfunction "1_1") (pintype "passive"))
    )
    (net (code "51") (name "Net-(P4-Pad2)") (class "Default")
      (node (ref "P4") (pin "2") (pinfunction "2_2") (pintype "passive"))
      (node (ref "R11") (pin "1") (pinfunction "1_1") (pintype "passive"))
    )
    (net (code "52") (name "Net-(P4-Pad3)") (class "Default")
      (node (ref "P4") (pin "3") (pinfunction "3_3") (pintype "passive"))
      (node (ref "R5") (pin "1") (pinfunction "1_1") (pintype "passive"))
    )
    (net (code "53") (name "Net-(P4-Pad4)") (class "Default")
      (node (ref "P4") (pin "4") (pinfunction "4_4") (pintype "passive"))
      (node (ref "R14") (pin "1") (pinfunction "1_1") (pintype "passive"))
    )
    (net (code "54") (name "Net-(P6-Pad1)") (class "Default")
      (node (ref "P6") (pin "1") (pinfunction "1_1") (pintype "passive"))
      (node (ref "RN5") (pin "7") (pinfunction "1_7") (pintype "passive"))
    )
    (net (code "55") (name "Net-(P6-Pad2)") (class "Default")
      (node (ref "P6") (pin "2") (pinfunction "2_2") (pintype "passive"))
      (node (ref "RN5") (pin "5") (pinfunction "5_5") (pintype "passive"))
    )
    (net (code "56") (name "Net-(P6-Pad3)") (class "Default")
      (node (ref "P6") (pin "3") (pinfunction "3_3") (pintype "passive"))
      (node (ref "RN5") (pin "3") (pinfunction "3_3") (pintype "passive"))
    )
    (net (code "57") (name "Net-(P6-Pad4)") (class "Default")
      (node (ref "P6") (pin "4") (pinfunction "4_4") (pintype "passive"))
      (node (ref "RN5") (pin "1") (pinfunction "1_1") (pintype "passive"))
    )
    (net (code "58") (name "Net-(P6-Pad5)") (class "Default")
      (node (ref "P6") (pin "5") (pinfunction "5_5") (pintype "passive"))
      (node (ref "RN6") (pin "7") (pinfunction "1_7") (pintype "passive"))
    )
    (net (code "59") (name "Net-(P6-Pad6)") (class "Default")
      (node (ref "P6") (pin "6") (pinfunction "6_6") (pintype "passive"))
      (node (ref "RN6") (pin "5") (pinfunction "5_5") (pintype "passive"))
    )
    (net (code "60") (name "Net-(P6-Pad7)") (class "Default")
      (node (ref "P6") (pin "7") (pinfunction "7_7") (pintype "passive"))
      (node (ref "RN6") (pin "3") (pinfunction "3_3") (pintype "passive"))
    )
    (net (code "61") (name "Net-(P6-Pad8)") (class "Default")
      (node (ref "P6") (pin "8") (pinfunction "8_8") (pintype "passive"))
      (node (ref "RN6") (pin "1") (pinfunction "1_1") (pintype "passive"))
    )
    (net (code "62") (name "Net-(P6-Pad9)") (class "Default")
      (node (ref "P6") (pin "9") (pinfunction "9_9") (pintype "passive"))
      (node (ref "RN7") (pin "7") (pinfunction "1_7") (pintype "passive"))
    )
    (net (code "63") (name "Net-(P6-Pad10)") (class "Default")
      (node (ref "P6") (pin "10") (pinfunction "10_10") (pintype "passive"))
      (node (ref "RN7") (pin "5") (pinfunction "5_5") (pintype "passive"))
    )
    (net (code "64") (name "Net-(P6-Pad11)") (class "Default")
      (node (ref "P6") (pin "11") (pinfunction "11_11") (pintype "passive"))
      (node (ref "RN7") (pin "3") (pinfunction "3_3") (pintype "passive"))
    )
    (net (code "65") (name "Net-(P6-Pad12)") (class "Default")
      (node (ref "P6") (pin "12") (pinfunction "12_12") (pintype "passive"))
      (node (ref "RN7") (pin "1") (pinfunction "1_1") (pintype "passive"))
    )
    (net (code "66") (name "Net-(S1-A1)") (class "Default")
      (node (ref "P1") (pin "1") (pinfunction "1_1") (pintype "passive"))
      (node (ref "RN3") (pin "7") (pinfunction "1_7") (pintype "passive"))
      (node (ref "S1") (pin "1") (pinfunction "A1_1") (pintype "passive"))
    )
    (net (code "67") (name "Net-(S1-A2)") (class "Default")
      (node (ref "P1") (pin "2") (pinfunction "2_2") (pintype "passive"))
      (node (ref "RN3") (pin "5") (pinfunction "5_5") (pintype "passive"))
      (node (ref "S1") (pin "2") (pinfunction "A2_2") (pintype "passive"))
    )
    (net (code "68") (name "Net-(S1-A3)") (class "Default")
      (node (ref "P1") (pin "3") (pinfunction "3_3") (pintype "passive"))
      (node (ref "RN3") (pin "3") (pinfunction "3_3") (pintype "passive"))
      (node (ref "S1") (pin "3") (pinfunction "A3_3") (pintype "passive"))
    )
    (net (code "69") (name "Net-(S1-A4)") (class "Default")
      (node (ref "P1") (pin "4") (pinfunction "4_4") (pintype "passive"))
      (node (ref "RN3") (pin "1") (pinfunction "1_1") (pintype "passive"))
      (node (ref "S1") (pin "4") (pinfunction "A4_4") (pintype "passive"))
    )
    (net (code "70") (name "Net-(S1-A5)") (class "Default")
      (node (ref "P1") (pin "5") (pinfunction "5_5") (pintype "passive"))
      (node (ref "RN4") (pin "7") (pinfunction "1_7") (pintype "passive"))
      (node (ref "S1") (pin "5") (pinfunction "A5_5") (pintype "passive"))
    )
    (net (code "71") (name "Net-(S1-A6)") (class "Default")
      (node (ref "P1") (pin "6") (pinfunction "6_6") (pintype "passive"))
      (node (ref "RN4") (pin "5") (pinfunction "5_5") (pintype "passive"))
      (node (ref "S1") (pin "6") (pinfunction "A6_6") (pintype "passive"))
    )
    (net (code "72") (name "Net-(S1-A7)") (class "Default")
      (node (ref "P1") (pin "7") (pinfunction "7_7") (pintype "passive"))
      (node (ref "RN4") (pin "3") (pinfunction "3_3") (pintype "passive"))
      (node (ref "S1") (pin "7") (pinfunction "A7_7") (pintype "passive"))
    )
    (net (code "73") (name "Net-(S1-A8)") (class "Default")
      (node (ref "P1") (pin "8") (pinfunction "8_8") (pintype "passive"))
      (node (ref "RN4") (pin "1") (pinfunction "1_1") (pintype "passive"))
      (node (ref "S1") (pin "8") (pinfunction "A8_8") (pintype "passive"))
    )
    (net (code "74") (name "Net-(S1-B1)") (class "Default")
      (node (ref "RN1") (pin "8") (pinfunction "8_8") (pintype "passive"))
      (node (ref "S1") (pin "16") (pinfunction "B1_16") (pintype "passive"))
    )
    (net (code "75") (name "Net-(S1-B2)") (class "Default")
      (node (ref "RN1") (pin "6") (pinfunction "6_6") (pintype "passive"))
      (node (ref "S1") (pin "15") (pinfunction "B2_15") (pintype "passive"))
    )
    (net (code "76") (name "Net-(S1-B3)") (class "Default")
      (node (ref "RN1") (pin "4") (pinfunction "4_4") (pintype "passive"))
      (node (ref "S1") (pin "14") (pinfunction "B3_14") (pintype "passive"))
    )
    (net (code "77") (name "Net-(S1-B4)") (class "Default")
      (node (ref "RN1") (pin "2") (pinfunction "2_2") (pintype "passive"))
      (node (ref "S1") (pin "13") (pinfunction "B4_13") (pintype "passive"))
    )
    (net (code "78") (name "Net-(S1-B5)") (class "Default")
      (node (ref "RN2") (pin "8") (pinfunction "8_8") (pintype "passive"))
      (node (ref "S1") (pin "12") (pinfunction "B5_12") (pintype "passive"))
    )
    (net (code "79") (name "Net-(S1-B6)") (class "Default")
      (node (ref "RN2") (pin "6") (pinfunction "6_6") (pintype "passive"))
      (node (ref "S1") (pin "11") (pinfunction "B6_11") (pintype "passive"))
    )
    (net (code "80") (name "Net-(S1-B7)") (class "Default")
      (node (ref "RN2") (pin "4") (pinfunction "4_4") (pintype "passive"))
      (node (ref "S1") (pin "10") (pinfunction "B7_10") (pintype "passive"))
    )
    (net (code "81") (name "Net-(S1-B8)") (class "Default")
      (node (ref "RN2") (pin "2") (pinfunction "2_2") (pintype "passive"))
      (node (ref "S1") (pin "9") (pinfunction "B8_9") (pintype "passive"))
    )
    (net (code "82") (name "Net-(S2-COM)") (class "Default")
      (node (ref "S2") (pin "2") (pinfunction "COM_2") (pintype "passive"))
      (node (ref "U3") (pin "7") (pinfunction "~{WC}_7") (pintype "input"))
    )
    (net (code "83") (name "Net-(U1-IN-)") (class "Default")
      (node (ref "R1") (pin "1") (pinfunction "1_1") (pintype "passive"))
      (node (ref "R2") (pin "2") (pinfunction "2_2") (pintype "passive"))
      (node (ref "U1") (pin "2") (pinfunction "IN-_2") (pintype "input"))
    )
    (net (code "84") (name "Net-(U1-OUT)") (class "Default")
      (node (ref "R1") (pin "2") (pinfunction "2_2") (pintype "passive"))
      (node (ref "RN1") (pin "1") (pinfunction "1_1") (pintype "passive"))
      (node (ref "RN1") (pin "3") (pinfunction "3_3") (pintype "passive"))
      (node (ref "RN1") (pin "5") (pinfunction "5_5") (pintype "passive"))
      (node (ref "RN1") (pin "7") (pinfunction "1_7") (pintype "passive"))
      (node (ref "RN2") (pin "1") (pinfunction "1_1") (pintype "passive"))
      (node (ref "RN2") (pin "3") (pinfunction "3_3") (pintype "passive"))
      (node (ref "RN2") (pin "5") (pinfunction "5_5") (pintype "passive"))
      (node (ref "RN2") (pin "7") (pinfunction "1_7") (pintype "passive"))
      (node (ref "U1") (pin "6") (pinfunction "OUT_6") (pintype "output"))
    )
    (net (code "85") (name "Net-(U2A-IN-)") (class "Default")
      (node (ref "R3") (pin "1") (pinfunction "1_1") (pintype "passive"))
      (node (ref "R4") (pin "2") (pinfunction "2_2") (pintype "passive"))
      (node (ref "U2") (pin "2") (pinfunction "IN-_2") (pintype "input"))
    )
    (net (code "86") (name "Net-(U2A-OUT)") (class "Default")
      (node (ref "R3") (pin "2") (pinfunction "2_2") (pintype "passive"))
      (node (ref "R5") (pin "2") (pinfunction "2_2") (pintype "passive"))
      (node (ref "U2") (pin "1") (pinfunction "OUT_1") (pintype "output"))
    )
    (net (code "87") (name "Net-(U2B-IN-)") (class "Default")
      (node (ref "R6") (pin "1") (pinfunction "1_1") (pintype "passive"))
      (node (ref "R7") (pin "2") (pinfunction "2_2") (pintype "passive"))
      (node (ref "U2") (pin "6") (pinfunction "IN-_6") (pintype "input"))
    )
    (net (code "88") (name "Net-(U2B-OUT)") (class "Default")
      (node (ref "R6") (pin "2") (pinfunction "2_2") (pintype "passive"))
      (node (ref "R8") (pin "2") (pinfunction "2_2") (pintype "passive"))
      (node (ref "U2") (pin "7") (pinfunction "OUT_7") (pintype "output"))
    )
    (net (code "89") (name "Net-(U2C-IN-)") (class "Default")
      (node (ref "R10") (pin "2") (pinfunction "2_2") (pintype "passive"))
      (node (ref "R9") (pin "1") (pinfunction "1_1") (pintype "passive"))
      (node (ref "U2") (pin "11") (pinfunction "IN-_11") (pintype "input"))
    )
    (net (code "90") (name "Net-(U2C-OUT)") (class "Default")
      (node (ref "R11") (pin "2") (pinfunction "2_2") (pintype "passive"))
      (node (ref "R9") (pin "2") (pinfunction "2_2") (pintype "passive"))
      (node (ref "U2") (pin "10") (pinfunction "OUT_10") (pintype "output"))
    )
    (net (code "91") (name "Net-(U2D-IN-)") (class "Default")
      (node (ref "R12") (pin "1") (pinfunction "1_1") (pintype "passive"))
      (node (ref "R13") (pin "2") (pinfunction "2_2") (pintype "passive"))
      (node (ref "U2") (pin "15") (pinfunction "IN-_15") (pintype "input"))
    )
    (net (code "92") (name "Net-(U2D-OUT)") (class "Default")
      (node (ref "R12") (pin "2") (pinfunction "2_2") (pintype "passive"))
      (node (ref "R14") (pin "2") (pinfunction "2_2") (pintype "passive"))
      (node (ref "U2") (pin "16") (pinfunction "OUT_16") (pintype "output"))
    )
    (net (code "93") (name "unconnected-(J1-Pad7)") (class "Default")
      (node (ref "J1") (pin "7") (pinfunction "7_7") (pintype "passive"))
    )
    (net (code "94") (name "unconnected-(J1-Pad9)") (class "Default")
      (node (ref "J1") (pin "9") (pinfunction "9_9") (pintype "passive"))
    )
    (net (code "95") (name "unconnected-(J1-Pad23)") (class "Default")
      (node (ref "J1") (pin "23") (pinfunction "23_23") (pintype "passive"))
    )
    (net (code "96") (name "unconnected-(J1-Pad24)") (class "Default")
      (node (ref "J1") (pin "24") (pinfunction "24_24") (pintype "passive"))
    )
    (net (code "97") (name "unconnected-(J1-Pad25)") (class "Default")
      (node (ref "J1") (pin "25") (pinfunction "25_25") (pintype "passive"))
    )
    (net (code "98") (name "unconnected-(J1-Pad26)") (class "Default")
      (node (ref "J1") (pin "26") (pinfunction "26_26") (pintype "passive"))
    )
    (net (code "99") (name "unconnected-(J1-Pad27)") (class "Default")
      (node (ref "J1") (pin "27") (pinfunction "27_27") (pintype "passive"))
    )
    (net (code "100") (name "unconnected-(J1-Pad28)") (class "Default")
      (node (ref "J1") (pin "28") (pinfunction "28_28") (pintype "passive"))
    )
    (net (code "101") (name "unconnected-(J1-Pad29)") (class "Default")
      (node (ref "J1") (pin "29") (pinfunction "29_29") (pintype "passive"))
    )
    (net (code "102") (name "unconnected-(J1-Pad30)") (class "Default")
      (node (ref "J1") (pin "30") (pinfunction "30_30") (pintype "passive"))
    )
    (net (code "103") (name "unconnected-(J1-Pad34)") (class "Default")
      (node (ref "J1") (pin "34") (pinfunction "34_34") (pintype "passive"))
    )
    (net (code "104") (name "unconnected-(J1-Pad36)") (class "Default")
      (node (ref "J1") (pin "36") (pinfunction "36_36") (pintype "passive"))
    )
    (net (code "105") (name "unconnected-(J1-Pad38)") (class "Default")
      (node (ref "J1") (pin "38") (pinfunction "38_38") (pintype "passive"))
    )
    (net (code "106") (name "unconnected-(J1-Pad40)") (class "Default")
      (node (ref "J1") (pin "40") (pinfunction "40_40") (pintype "passive"))
    )
    (net (code "107") (name "unconnected-(J1-Pad43)") (class "Default")
      (node (ref "J1") (pin "43") (pinfunction "43_43") (pintype "passive"))
    )
    (net (code "108") (name "unconnected-(J1-Pad45)") (class "Default")
      (node (ref "J1") (pin "45") (pinfunction "45_45") (pintype "passive"))
    )
    (net (code "109") (name "unconnected-(J1-Pad47)") (class "Default")
      (node (ref "J1") (pin "47") (pinfunction "47_47") (pintype "passive"))
    )
    (net (code "110") (name "unconnected-(J1-Pad49)") (class "Default")
      (node (ref "J1") (pin "49") (pinfunction "49_49") (pintype "passive+no_connect"))
    )
    (net (code "111") (name "unconnected-(J1-Pad75)") (class "Default")
      (node (ref "J1") (pin "75") (pinfunction "75_75") (pintype "passive"))
    )
    (net (code "112") (name "unconnected-(J1-Pad77)") (class "Default")
      (node (ref "J1") (pin "77") (pinfunction "77_77") (pintype "passive"))
    )
    (net (code "113") (name "unconnected-(J1-Pad79)") (class "Default")
      (node (ref "J1") (pin "79") (pinfunction "79_79") (pintype "passive"))
    )
    (net (code "114") (name "unconnected-(J1-Pad81)") (class "Default")
      (node (ref "J1") (pin "81") (pinfunction "81_81") (pintype "passive"))
    )
    (net (code "115") (name "unconnected-(J1-Pad85)") (class "Default")
      (node (ref "J1") (pin "85") (pinfunction "85_85") (pintype "passive"))
    )
    (net (code "116") (name "unconnected-(J1-Pad86)") (class "Default")
      (node (ref "J1") (pin "86") (pinfunction "86_86") (pintype "passive"))
    )
    (net (code "117") (name "unconnected-(J1-Pad87)") (class "Default")
      (node (ref "J1") (pin "87") (pinfunction "87_87") (pintype "passive"))
    )
    (net (code "118") (name "unconnected-(J1-Pad88)") (class "Default")
      (node (ref "J1") (pin "88") (pinfunction "88_88") (pintype "passive"))
    )
    (net (code "119") (name "unconnected-(J1-Pad89)") (class "Default")
      (node (ref "J1") (pin "89") (pinfunction "89_89") (pintype "passive"))
    )
    (net (code "120") (name "unconnected-(J1-Pad90)") (class "Default")
      (node (ref "J1") (pin "90") (pinfunction "90_90") (pintype "passive"))
    )
    (net (code "121") (name "unconnected-(J1-Pad91)") (class "Default")
      (node (ref "J1") (pin "91") (pinfunction "91_91") (pintype "passive"))
    )
    (net (code "122") (name "unconnected-(J1-Pad92)") (class "Default")
      (node (ref "J1") (pin "92") (pinfunction "92_92") (pintype "passive"))
    )
    (net (code "123") (name "unconnected-(J1-Pad95)") (class "Default")
      (node (ref "J1") (pin "95") (pinfunction "95_95") (pintype "passive"))
    )
    (net (code "124") (name "unconnected-(J1-Pad96)") (class "Default")
      (node (ref "J1") (pin "96") (pinfunction "96_96") (pintype "passive"))
    )
    (net (code "125") (name "unconnected-(J1-Pad97)") (class "Default")
      (node (ref "J1") (pin "97") (pinfunction "97_97") (pintype "passive"))
    )
    (net (code "126") (name "unconnected-(J1-Pad98)") (class "Default")
      (node (ref "J1") (pin "98") (pinfunction "98_98") (pintype "passive"))
    )
    (net (code "127") (name "unconnected-(J1-Pad99)") (class "Default")
      (node (ref "J1") (pin "99") (pinfunction "99_99") (pintype "passive"))
    )
    (net (code "128") (name "unconnected-(J1-Pad100)") (class "Default")
      (node (ref "J1") (pin "100") (pinfunction "100_100") (pintype "passive"))
    )
    (net (code "129") (name "unconnected-(J1-Pad101)") (class "Default")
      (node (ref "J1") (pin "101") (pinfunction "101_101") (pintype "passive"))
    )
    (net (code "130") (name "unconnected-(J1-Pad102)") (class "Default")
      (node (ref "J1") (pin "102") (pinfunction "102_102") (pintype "passive"))
    )
    (net (code "131") (name "unconnected-(U1-NC-Pad5)") (class "Default")
      (node (ref "U1") (pin "5") (pinfunction "NC_5") (pintype "passive"))
    )
    (net (code "132") (name "unconnected-(U1-VOSTRIM-Pad1)") (class "Default")
      (node (ref "U1") (pin "1") (pinfunction "VOSTRIM_1") (pintype "passive"))
    )
    (net (code "133") (name "unconnected-(U1-VOSTRIM-Pad8)") (class "Default")
      (node (ref "U1") (pin "8") (pinfunction "VOSTRIM_8") (pintype "passive"))
    )
  )
)
